# 07_LOAD.net
KiCad netlist of a schematic drawn in EAGLE
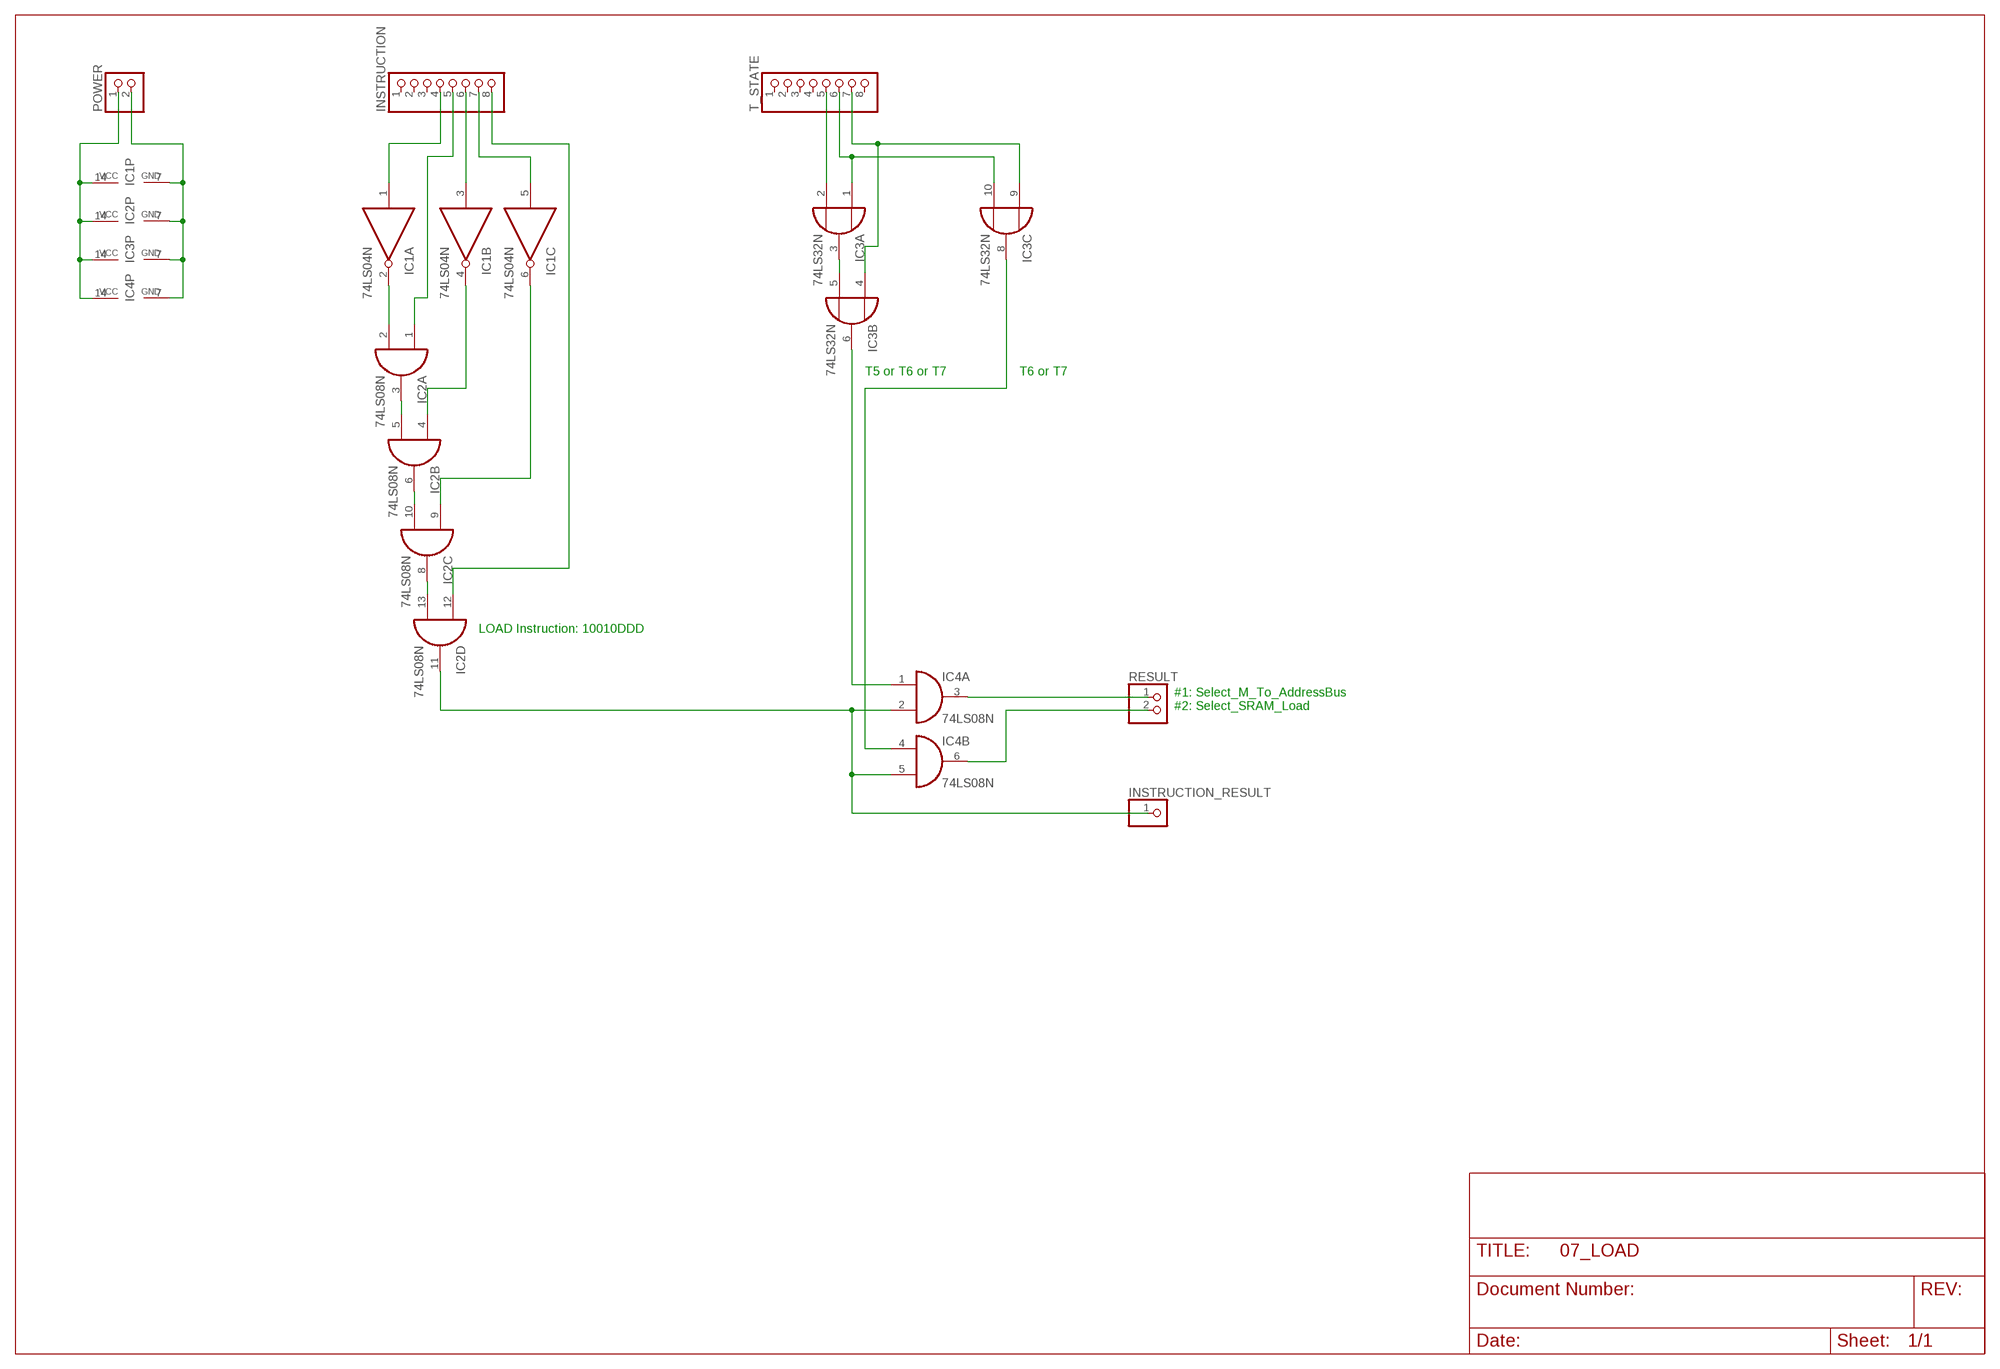
[diagram p0: schematic, sheet 1]

(export (version "E")
  (design (tool "Eeschema 10.0.6"))
  (components
    (comp (ref "IC1")
      (value "74LS04N")
      (footprint "eagle-import:DIL14")
      (libsource (lib "eagle-import") (part "7404NLS"))
    )
    (comp (ref "IC2")
      (value "74LS08N")
      (footprint "eagle-import:DIL14")
      (libsource (lib "eagle-import") (part "7408NLS"))
    )
    (comp (ref "IC3")
      (value "74LS32N")
      (footprint "eagle-import:DIL14")
      (libsource (lib "eagle-import") (part "7432NLS"))
    )
    (comp (ref "IC4")
      (value "74LS08N")
      (footprint "eagle-import:DIL14")
      (libsource (lib "eagle-import") (part "7408NLS"))
    )
    (comp (ref "INSTRUCTION")
      (value "PINHD-1X8")
      (footprint "eagle-import:1X08")
      (libsource (lib "eagle-import") (part "PINHD-1X8"))
    )
    (comp (ref "INSTRUCTION_RESULT")
      (value "PINHD-1X1")
      (footprint "eagle-import:1X01")
      (libsource (lib "eagle-import") (part "PINHD-1X1"))
    )
    (comp (ref "POWER")
      (value "PINHD-1X2")
      (footprint "eagle-import:1X02")
      (libsource (lib "eagle-import") (part "PINHD-1X2"))
    )
    (comp (ref "RESULT")
      (value "PINHD-1X2")
      (footprint "eagle-import:1X02")
      (libsource (lib "eagle-import") (part "PINHD-1X2"))
    )
    (comp (ref "T_STATE")
      (value "PINHD-1X8")
      (footprint "eagle-import:1X08")
      (libsource (lib "eagle-import") (part "PINHD-1X8"))
    )
  )
  (nets
    (net (code "1") (name "Net-(IC1A-I)") (class "Default")
      (node (ref "IC1") (pin "1") (pinfunction "I_1") (pintype "input"))
      (node (ref "INSTRUCTION") (pin "4") (pinfunction "4_4") (pintype "passive"))
    )
    (net (code "2") (name "Net-(IC1A-O)") (class "Default")
      (node (ref "IC1") (pin "2") (pinfunction "O_2") (pintype "output"))
      (node (ref "IC2") (pin "2") (pinfunction "I1_2") (pintype "input"))
    )
    (net (code "3") (name "Net-(IC1B-I)") (class "Default")
      (node (ref "IC1") (pin "3") (pinfunction "I_3") (pintype "input"))
      (node (ref "INSTRUCTION") (pin "6") (pinfunction "6_6") (pintype "passive"))
    )
    (net (code "4") (name "Net-(IC1B-O)") (class "Default")
      (node (ref "IC1") (pin "4") (pinfunction "O_4") (pintype "output"))
      (node (ref "IC2") (pin "4") (pinfunction "I0_4") (pintype "input"))
    )
    (net (code "5") (name "Net-(IC1C-I)") (class "Default")
      (node (ref "IC1") (pin "5") (pinfunction "I_5") (pintype "input"))
      (node (ref "INSTRUCTION") (pin "7") (pinfunction "7_7") (pintype "passive"))
    )
    (net (code "6") (name "Net-(IC1C-O)") (class "Default")
      (node (ref "IC1") (pin "6") (pinfunction "O_6") (pintype "output"))
      (node (ref "IC2") (pin "9") (pinfunction "I0_9") (pintype "input"))
    )
    (net (code "7") (name "Net-(IC1G-GND)") (class "Default")
      (node (ref "IC1") (pin "7") (pinfunction "GND_7") (pintype "power_in"))
      (node (ref "IC2") (pin "7") (pinfunction "GND_7") (pintype "power_in"))
      (node (ref "IC3") (pin "7") (pinfunction "GND_7") (pintype "power_in"))
      (node (ref "IC4") (pin "7") (pinfunction "GND_7") (pintype "power_in"))
      (node (ref "POWER") (pin "2") (pinfunction "2_2") (pintype "passive"))
    )
    (net (code "8") (name "Net-(IC1G-VCC)") (class "Default")
      (node (ref "IC1") (pin "14") (pinfunction "VCC_14") (pintype "power_in"))
      (node (ref "IC2") (pin "14") (pinfunction "VCC_14") (pintype "power_in"))
      (node (ref "IC3") (pin "14") (pinfunction "VCC_14") (pintype "power_in"))
      (node (ref "IC4") (pin "14") (pinfunction "VCC_14") (pintype "power_in"))
      (node (ref "POWER") (pin "1") (pinfunction "1_1") (pintype "passive"))
    )
    (net (code "9") (name "Net-(IC2A-I0)") (class "Default")
      (node (ref "IC2") (pin "1") (pinfunction "I0_1") (pintype "input"))
      (node (ref "INSTRUCTION") (pin "5") (pinfunction "5_5") (pintype "passive"))
    )
    (net (code "10") (name "Net-(IC2A-O)") (class "Default")
      (node (ref "IC2") (pin "3") (pinfunction "O_3") (pintype "output"))
      (node (ref "IC2") (pin "5") (pinfunction "I1_5") (pintype "input"))
    )
    (net (code "11") (name "Net-(IC2B-O)") (class "Default")
      (node (ref "IC2") (pin "10") (pinfunction "I1_10") (pintype "input"))
      (node (ref "IC2") (pin "6") (pinfunction "O_6") (pintype "output"))
    )
    (net (code "12") (name "Net-(IC2C-O)") (class "Default")
      (node (ref "IC2") (pin "13") (pinfunction "I1_13") (pintype "input"))
      (node (ref "IC2") (pin "8") (pinfunction "O_8") (pintype "output"))
    )
    (net (code "13") (name "Net-(IC2D-I0)") (class "Default")
      (node (ref "IC2") (pin "12") (pinfunction "I0_12") (pintype "input"))
      (node (ref "INSTRUCTION") (pin "8") (pinfunction "8_8") (pintype "passive"))
    )
    (net (code "14") (name "Net-(IC2D-O)") (class "Default")
      (node (ref "IC2") (pin "11") (pinfunction "O_11") (pintype "output"))
      (node (ref "IC4") (pin "2") (pinfunction "I1_2") (pintype "input"))
      (node (ref "IC4") (pin "5") (pinfunction "I1_5") (pintype "input"))
      (node (ref "INSTRUCTION_RESULT") (pin "1") (pinfunction "1_1") (pintype "passive"))
    )
    (net (code "15") (name "Net-(IC3A-I0)") (class "Default")
      (node (ref "IC3") (pin "1") (pinfunction "I0_1") (pintype "input"))
      (node (ref "IC3") (pin "10") (pinfunction "I1_10") (pintype "input"))
      (node (ref "T_STATE") (pin "6") (pinfunction "6_6") (pintype "passive"))
    )
    (net (code "16") (name "Net-(IC3A-I1)") (class "Default")
      (node (ref "IC3") (pin "2") (pinfunction "I1_2") (pintype "input"))
      (node (ref "T_STATE") (pin "5") (pinfunction "5_5") (pintype "passive"))
    )
    (net (code "17") (name "Net-(IC3A-O)") (class "Default")
      (node (ref "IC3") (pin "3") (pinfunction "O_3") (pintype "output"))
      (node (ref "IC3") (pin "5") (pinfunction "I1_5") (pintype "input"))
    )
    (net (code "18") (name "Net-(IC3B-I0)") (class "Default")
      (node (ref "IC3") (pin "4") (pinfunction "I0_4") (pintype "input"))
      (node (ref "IC3") (pin "9") (pinfunction "I0_9") (pintype "input"))
      (node (ref "T_STATE") (pin "7") (pinfunction "7_7") (pintype "passive"))
    )
    (net (code "19") (name "Net-(IC3B-O)") (class "Default")
      (node (ref "IC3") (pin "6") (pinfunction "O_6") (pintype "output"))
      (node (ref "IC4") (pin "1") (pinfunction "I0_1") (pintype "input"))
    )
    (net (code "20") (name "Net-(IC3C-O)") (class "Default")
      (node (ref "IC3") (pin "8") (pinfunction "O_8") (pintype "output"))
      (node (ref "IC4") (pin "4") (pinfunction "I0_4") (pintype "input"))
    )
    (net (code "21") (name "Net-(IC4A-O)") (class "Default")
      (node (ref "IC4") (pin "3") (pinfunction "O_3") (pintype "output"))
      (node (ref "RESULT") (pin "1") (pinfunction "1_1") (pintype "passive"))
    )
    (net (code "22") (name "Net-(IC4B-O)") (class "Default")
      (node (ref "IC4") (pin "6") (pinfunction "O_6") (pintype "output"))
      (node (ref "RESULT") (pin "2") (pinfunction "2_2") (pintype "passive"))
    )
    (net (code "23") (name "unconnected-(INSTRUCTION-Pad1)") (class "Default")
      (node (ref "INSTRUCTION") (pin "1") (pinfunction "1_1") (pintype "passive"))
    )
    (net (code "24") (name "unconnected-(INSTRUCTION-Pad2)") (class "Default")
      (node (ref "INSTRUCTION") (pin "2") (pinfunction "2_2") (pintype "passive"))
    )
    (net (code "25") (name "unconnected-(INSTRUCTION-Pad3)") (class "Default")
      (node (ref "INSTRUCTION") (pin "3") (pinfunction "3_3") (pintype "passive"))
    )
    (net (code "26") (name "unconnected-(T_STATE-Pad1)") (class "Default")
      (node (ref "T_STATE") (pin "1") (pinfunction "1_1") (pintype "passive"))
    )
    (net (code "27") (name "unconnected-(T_STATE-Pad2)") (class "Default")
      (node (ref "T_STATE") (pin "2") (pinfunction "2_2") (pintype "passive"))
    )
    (net (code "28") (name "unconnected-(T_STATE-Pad3)") (class "Default")
      (node (ref "T_STATE") (pin "3") (pinfunction "3_3") (pintype "passive"))
    )
    (net (code "29") (name "unconnected-(T_STATE-Pad4)") (class "Default")
      (node (ref "T_STATE") (pin "4") (pinfunction "4_4") (pintype "passive"))
    )
    (net (code "30") (name "unconnected-(T_STATE-Pad8)") (class "Default")
      (node (ref "T_STATE") (pin "8") (pinfunction "8_8") (pintype "passive"))
    )
  )
)
